# DB10012_ControlPower.net
KiCad netlist of a schematic drawn in Altium Designer
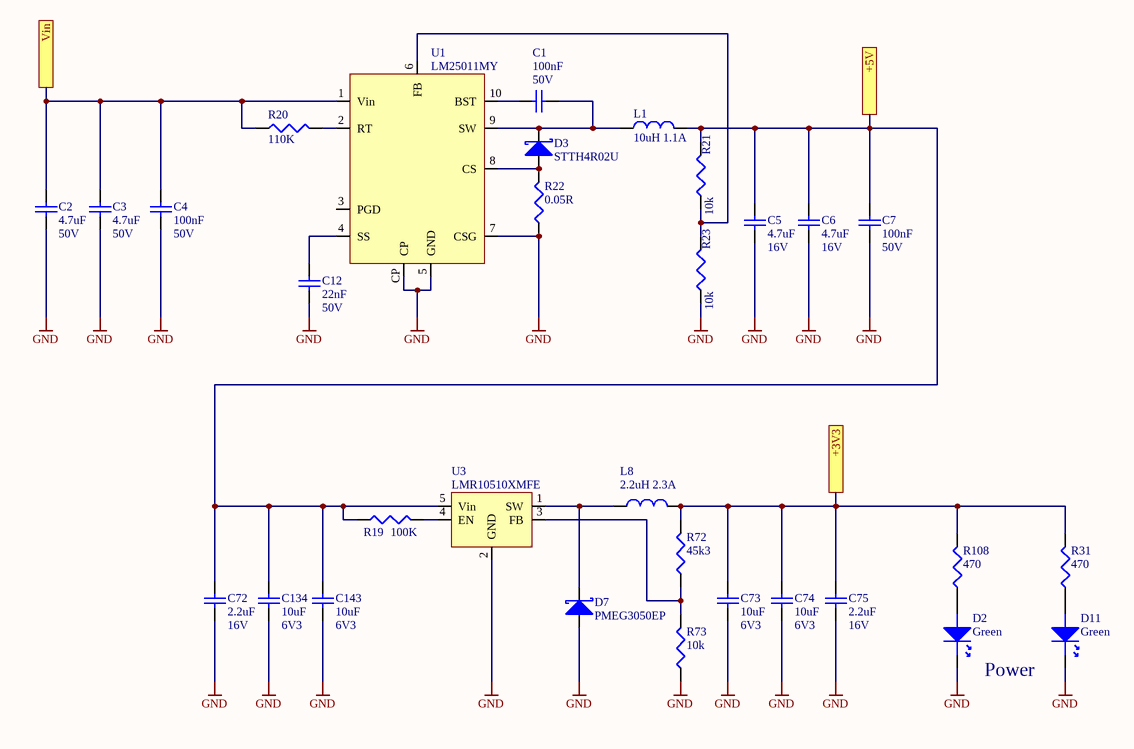
[diagram p0: DB10012_ControlPower.SchDoc]

(export (version "E")
  (design (tool "Eeschema 10.0.6"))
  (components
    (comp (ref "C1")
      (value "100nF")
      (footprint "C-0805")
      (description "Capacitor, 100nF, 50V,  X7R")
      (fields (field (name "VOLTAGE RATING") "50V"))
      (libsource (lib "AR_Capacitors_Ceramic") (part "100nF/0805/CER/50V"))
    )
    (comp (ref "C2")
      (value "4.7uF")
      (footprint "C-1206")
      (description "Capacitor, 4.7uF, 50V, X7R")
      (fields (field (name "VOLTAGE RATING") "50V"))
      (libsource (lib "AR_Capacitors_Ceramic") (part "4.7uF/1206/CER/50V"))
    )
    (comp (ref "C3")
      (value "4.7uF")
      (footprint "C-1206")
      (description "Capacitor, 4.7uF, 50V, X7R")
      (fields (field (name "VOLTAGE RATING") "50V"))
      (libsource (lib "AR_Capacitors_Ceramic") (part "4.7uF/1206/CER/50V"))
    )
    (comp (ref "C4")
      (value "100nF")
      (footprint "C-0805")
      (description "Capacitor, 100nF, 50V,  X7R")
      (fields (field (name "VOLTAGE RATING") "50V"))
      (libsource (lib "AR_Capacitors_Ceramic") (part "100nF/0805/CER/50V"))
    )
    (comp (ref "C5")
      (value "4.7uF")
      (footprint "C-0805")
      (description "Capacitor, 4.7uF, 16V, X7R")
      (fields (field (name "VOLTAGE RATING") "16V"))
      (libsource (lib "AR_Capacitors_Ceramic") (part "4.7uF/0805/CER/16V"))
    )
    (comp (ref "C6")
      (value "4.7uF")
      (footprint "C-0805")
      (description "Capacitor, 4.7uF, 16V, X7R")
      (fields (field (name "VOLTAGE RATING") "16V"))
      (libsource (lib "AR_Capacitors_Ceramic") (part "4.7uF/0805/CER/16V"))
    )
    (comp (ref "C7")
      (value "100nF")
      (footprint "C-0805")
      (description "Capacitor, 100nF, 50V,  X7R")
      (fields (field (name "VOLTAGE RATING") "50V"))
      (libsource (lib "AR_Capacitors_Ceramic") (part "100nF/0805/CER/50V"))
    )
    (comp (ref "C12")
      (value "22nF")
      (footprint "C0402")
      (description "Capacitor, 22nF, 50V, X7R")
      (fields (field (name "VOLTAGE RATING") "50V"))
      (libsource (lib "AR_Capacitors_Ceramic") (part "22nF/0402/CER/50V"))
    )
    (comp (ref "C72")
      (value "2.2uF")
      (footprint "C0603")
      (description "Capacitor, 2.2uF, 16V, X5R")
      (fields (field (name "VOLTAGE RATING") "16V"))
      (libsource (lib "AR_Capacitors_Ceramic") (part "2.2uF/0603/CER/16V"))
    )
    (comp (ref "C73")
      (value "10uF")
      (footprint "C0603")
      (description "Capacitor, 10uF, 6.3V, X5R")
      (fields (field (name "VOLTAGE RATING") "6V3"))
      (libsource (lib "AR_Capacitors_Ceramic") (part "10uF/0603/CER/6V3/X5R"))
    )
    (comp (ref "C74")
      (value "10uF")
      (footprint "C0603")
      (description "Capacitor, 10uF, 6.3V, X5R")
      (fields (field (name "VOLTAGE RATING") "6V3"))
      (libsource (lib "AR_Capacitors_Ceramic") (part "10uF/0603/CER/6V3/X5R"))
    )
    (comp (ref "C75")
      (value "2.2uF")
      (footprint "C0603")
      (description "Capacitor, 2.2uF, 16V, X5R")
      (fields (field (name "VOLTAGE RATING") "16V"))
      (libsource (lib "AR_Capacitors_Ceramic") (part "2.2uF/0603/CER/16V"))
    )
    (comp (ref "C134")
      (value "10uF")
      (footprint "C-0805")
      (description "Capacitor, 10uF, 6.3V, X7R")
      (fields (field (name "VOLTAGE RATING") "6V3"))
      (libsource (lib "AR_Capacitors_Ceramic") (part "10uF/0805/CER/6V3"))
    )
    (comp (ref "C143")
      (value "10uF")
      (footprint "C-0805")
      (description "Capacitor, 10uF, 6.3V, X7R")
      (fields (field (name "VOLTAGE RATING") "6V3"))
      (libsource (lib "AR_Capacitors_Ceramic") (part "10uF/0805/CER/6V3"))
    )
    (comp (ref "D2")
      (value "Green")
      (footprint "D-0805")
      (description "Led, Green, Li:12mcd, Vf:2.2V, If:0.02A")
      (libsource (lib "AR_Misc") (part "KP-2012SGC"))
    )
    (comp (ref "D3")
      (value "STTH4R02U")
      (footprint "CASE 403A-03")
      (description "Diode Schottky, Vrrm: 200V, If: 4A, Vf: 1,05V")
      (libsource (lib "AR_Diodes") (part "STTH4R02U"))
    )
    (comp (ref "D7")
      (value "PMEG3050EP")
      (footprint "SOD128")
      (description "Diode Schottky, Vrrm: 30V, If: 3A, Vf: 0.36V")
      (libsource (lib "AR_Diodes") (part "PMEG3050EP"))
    )
    (comp (ref "D11")
      (value "Green")
      (footprint "D-0805")
      (description "Led, Green, Li:12mcd, Vf:2.2V, If:0.02A")
      (libsource (lib "AR_Misc") (part "KP-2012SGC"))
    )
    (comp (ref "L1")
      (value "10uH 1.1A")
      (footprint "WE-TPC 5818, L")
      (description "10UH, 30%, 1.1A")
      (libsource (lib "AR_Inductors") (part "744052100"))
    )
    (comp (ref "L8")
      (value "2.2uH 2.3A")
      (footprint "SRN2512")
      (description "2.2UH, 20%, 2.3A")
      (libsource (lib "AR_Inductors") (part "SRN2512-2R2M"))
    )
    (comp (ref "R19")
      (value "100K")
      (footprint "0402")
      (description "Resistor, 100k, 0.1%, 0.0625W, 50V, 100PPM, 0402")
      (libsource (lib "AR_Resistors_SMD") (part "100k/0402/0063W/50V"))
    )
    (comp (ref "R20")
      (value "110K")
      (footprint "0603")
      (description "Resistor, 110K, 0.1%, 0.1W, 75V, 25PPM, 0603")
      (libsource (lib "AR_Resistors_SMD") (part "110K/0603/0100W/75V"))
    )
    (comp (ref "R21")
      (value "10k")
      (footprint "0402")
      (description "Resistor, 10k, 0.1%, 0.0625W, 50V, 100PPM, 0402")
      (libsource (lib "AR_Resistors_SMD") (part "10k/0402/0063W/50V"))
    )
    (comp (ref "R22")
      (value "0.05R")
      (footprint "0805")
      (description "Resistor, 0.05R, 1%, 0.125W, 150V, 100PPM, 0805")
      (libsource (lib "AR_Resistors_SMD") (part "0.05/0805/0125W/150V"))
    )
    (comp (ref "R23")
      (value "10k")
      (footprint "0402")
      (description "Resistor, 10k, 0.1%, 0.0625W, 50V, 100PPM, 0402")
      (libsource (lib "AR_Resistors_SMD") (part "10k/0402/0063W/50V"))
    )
    (comp (ref "R31")
      (value "470")
      (footprint "0402")
      (description "Resistor, 470, 1%, 0.0625W, 50V, 100PPM, 0402")
      (libsource (lib "AR_Resistors_SMD") (part "470/0402/0063W/50V"))
    )
    (comp (ref "R72")
      (value "45k3")
      (footprint "0402")
      (description "Resistor, 45K3, 0.1%, 0.0625W, 50V, 100PPM, 0402")
      (libsource (lib "AR_Resistors_SMD") (part "45k3/0402/0063W/50V"))
    )
    (comp (ref "R73")
      (value "10k")
      (footprint "0402")
      (description "Resistor, 10k, 0.1%, 0.0625W, 50V, 100PPM, 0402")
      (libsource (lib "AR_Resistors_SMD") (part "10k/0402/0063W/50V"))
    )
    (comp (ref "R108")
      (value "470")
      (footprint "0402")
      (description "Resistor, 470, 1%, 0.0625W, 50V, 100PPM, 0402")
      (libsource (lib "AR_Resistors_SMD") (part "470/0402/0063W/50V"))
    )
    (comp (ref "U1")
      (value "LM25011MY")
      (footprint "MUC10A")
      (description "STEP-DOWN REGULATOR, MSOP-10")
      (libsource (lib "AR_Vreg") (part "LM25011MY"))
    )
    (comp (ref "U3")
      (value "LMR10510XMFE")
      (footprint "SOT-23-5")
      (description "DC/DC CONV, BUCK, 1.95MHZ, SOT-23-5")
      (libsource (lib "AR_Vreg") (part "LMR10510XMFE"))
    )
  )
  (nets
    (net (code "1") (name "/+3V3") (class "Default")
      (node (ref "C73") (pin "1") (pinfunction "1_1") (pintype "passive"))
      (node (ref "C74") (pin "1") (pinfunction "1_1") (pintype "passive"))
      (node (ref "C75") (pin "2") (pinfunction "2_2") (pintype "passive"))
      (node (ref "L8") (pin "1") (pinfunction "1_1") (pintype "passive"))
      (node (ref "R108") (pin "2") (pinfunction "2_2") (pintype "passive"))
      (node (ref "R31") (pin "2") (pinfunction "2_2") (pintype "passive"))
      (node (ref "R72") (pin "2") (pinfunction "2_2") (pintype "passive"))
    )
    (net (code "2") (name "/+5V") (class "Default")
      (node (ref "C134") (pin "1") (pinfunction "1_1") (pintype "passive"))
      (node (ref "C143") (pin "1") (pinfunction "1_1") (pintype "passive"))
      (node (ref "C5") (pin "2") (pinfunction "2_2") (pintype "passive"))
      (node (ref "C6") (pin "2") (pinfunction "2_2") (pintype "passive"))
      (node (ref "C7") (pin "2") (pinfunction "2_2") (pintype "passive"))
      (node (ref "C72") (pin "2") (pinfunction "2_2") (pintype "passive"))
      (node (ref "L1") (pin "2") (pinfunction "2_2") (pintype "passive"))
      (node (ref "R19") (pin "1") (pinfunction "1_1") (pintype "passive"))
      (node (ref "R21") (pin "2") (pinfunction "2_2") (pintype "passive"))
      (node (ref "U3") (pin "5") (pinfunction "Vin_5") (pintype "passive"))
    )
    (net (code "3") (name "/Vin") (class "Default")
      (node (ref "C2") (pin "2") (pinfunction "2_2") (pintype "passive"))
      (node (ref "C3") (pin "2") (pinfunction "2_2") (pintype "passive"))
      (node (ref "C4") (pin "2") (pinfunction "2_2") (pintype "passive"))
      (node (ref "R20") (pin "1") (pinfunction "1_1") (pintype "passive"))
      (node (ref "U1") (pin "1") (pinfunction "Vin_1") (pintype "passive"))
    )
    (net (code "4") (name "GND") (class "Default")
      (node (ref "C12") (pin "1") (pinfunction "1_1") (pintype "passive"))
      (node (ref "C134") (pin "2") (pinfunction "2_2") (pintype "passive"))
      (node (ref "C143") (pin "2") (pinfunction "2_2") (pintype "passive"))
      (node (ref "C2") (pin "1") (pinfunction "1_1") (pintype "passive"))
      (node (ref "C3") (pin "1") (pinfunction "1_1") (pintype "passive"))
      (node (ref "C4") (pin "1") (pinfunction "1_1") (pintype "passive"))
      (node (ref "C5") (pin "1") (pinfunction "1_1") (pintype "passive"))
      (node (ref "C6") (pin "1") (pinfunction "1_1") (pintype "passive"))
      (node (ref "C7") (pin "1") (pinfunction "1_1") (pintype "passive"))
      (node (ref "C72") (pin "1") (pinfunction "1_1") (pintype "passive"))
      (node (ref "C73") (pin "2") (pinfunction "2_2") (pintype "passive"))
      (node (ref "C74") (pin "2") (pinfunction "2_2") (pintype "passive"))
      (node (ref "C75") (pin "1") (pinfunction "1_1") (pintype "passive"))
      (node (ref "D11") (pin "K") (pinfunction "K_K") (pintype "passive"))
      (node (ref "D2") (pin "K") (pinfunction "K_K") (pintype "passive"))
      (node (ref "D7") (pin "1") (pinfunction "A_1") (pintype "passive"))
      (node (ref "R22") (pin "1") (pinfunction "1_1") (pintype "passive"))
      (node (ref "R23") (pin "1") (pinfunction "1_1") (pintype "passive"))
      (node (ref "R73") (pin "1") (pinfunction "1_1") (pintype "passive"))
      (node (ref "U1") (pin "5") (pinfunction "GND_5") (pintype "passive"))
      (node (ref "U1") (pin "7") (pinfunction "CSG_7") (pintype "power_in"))
      (node (ref "U1") (pin "CP") (pinfunction "CP_CP") (pintype "power_in"))
      (node (ref "U3") (pin "2") (pinfunction "GND_2") (pintype "passive"))
    )
    (net (code "5") (name "Net-(D2-PadA)") (class "Default")
      (node (ref "D2") (pin "A") (pinfunction "A_A") (pintype "passive"))
      (node (ref "R108") (pin "1") (pinfunction "1_1") (pintype "passive"))
    )
    (net (code "6") (name "Net-(D3-A)") (class "Default")
      (node (ref "D3") (pin "1") (pinfunction "A_1") (pintype "passive"))
      (node (ref "R22") (pin "2") (pinfunction "2_2") (pintype "passive"))
      (node (ref "U1") (pin "8") (pinfunction "CS_8") (pintype "power_in"))
    )
    (net (code "7") (name "Net-(D3-K)") (class "Default")
      (node (ref "C1") (pin "2") (pinfunction "2_2") (pintype "passive"))
      (node (ref "D3") (pin "2") (pinfunction "K_2") (pintype "passive"))
      (node (ref "L1") (pin "1") (pinfunction "1_1") (pintype "passive"))
      (node (ref "U1") (pin "9") (pinfunction "SW_9") (pintype "power_in"))
    )
    (net (code "8") (name "Net-(D7-K)") (class "Default")
      (node (ref "D7") (pin "2") (pinfunction "K_2") (pintype "passive"))
      (node (ref "L8") (pin "0") (pinfunction "0_0") (pintype "passive"))
      (node (ref "U3") (pin "1") (pinfunction "SW_1") (pintype "passive"))
    )
    (net (code "9") (name "Net-(D11-PadA)") (class "Default")
      (node (ref "D11") (pin "A") (pinfunction "A_A") (pintype "passive"))
      (node (ref "R31") (pin "1") (pinfunction "1_1") (pintype "passive"))
    )
    (net (code "10") (name "Net-(U1-BST)") (class "Default")
      (node (ref "C1") (pin "1") (pinfunction "1_1") (pintype "passive"))
      (node (ref "U1") (pin "10") (pinfunction "BST_10") (pintype "power_in"))
    )
    (net (code "11") (name "Net-(U1-FB)") (class "Default")
      (node (ref "R21") (pin "1") (pinfunction "1_1") (pintype "passive"))
      (node (ref "R23") (pin "2") (pinfunction "2_2") (pintype "passive"))
      (node (ref "U1") (pin "6") (pinfunction "FB_6") (pintype "passive"))
    )
    (net (code "12") (name "Net-(U1-RT)") (class "Default")
      (node (ref "R20") (pin "2") (pinfunction "2_2") (pintype "passive"))
      (node (ref "U1") (pin "2") (pinfunction "RT_2") (pintype "power_in"))
    )
    (net (code "13") (name "Net-(U1-SS)") (class "Default")
      (node (ref "C12") (pin "2") (pinfunction "2_2") (pintype "passive"))
      (node (ref "U1") (pin "4") (pinfunction "SS_4") (pintype "power_in"))
    )
    (net (code "14") (name "Net-(U3-EN)") (class "Default")
      (node (ref "R19") (pin "2") (pinfunction "2_2") (pintype "passive"))
      (node (ref "U3") (pin "4") (pinfunction "EN_4") (pintype "passive"))
    )
    (net (code "15") (name "Net-(U3-FB)") (class "Default")
      (node (ref "R72") (pin "1") (pinfunction "1_1") (pintype "passive"))
      (node (ref "R73") (pin "2") (pinfunction "2_2") (pintype "passive"))
      (node (ref "U3") (pin "3") (pinfunction "FB_3") (pintype "passive"))
    )
    (net (code "16") (name "unconnected-(U1-PGD-Pad3)") (class "Default")
      (node (ref "U1") (pin "3") (pinfunction "PGD_3") (pintype "power_in"))
    )
  )
)
